# ESP_Updater.net
KiCad netlist of a schematic drawn in EAGLE
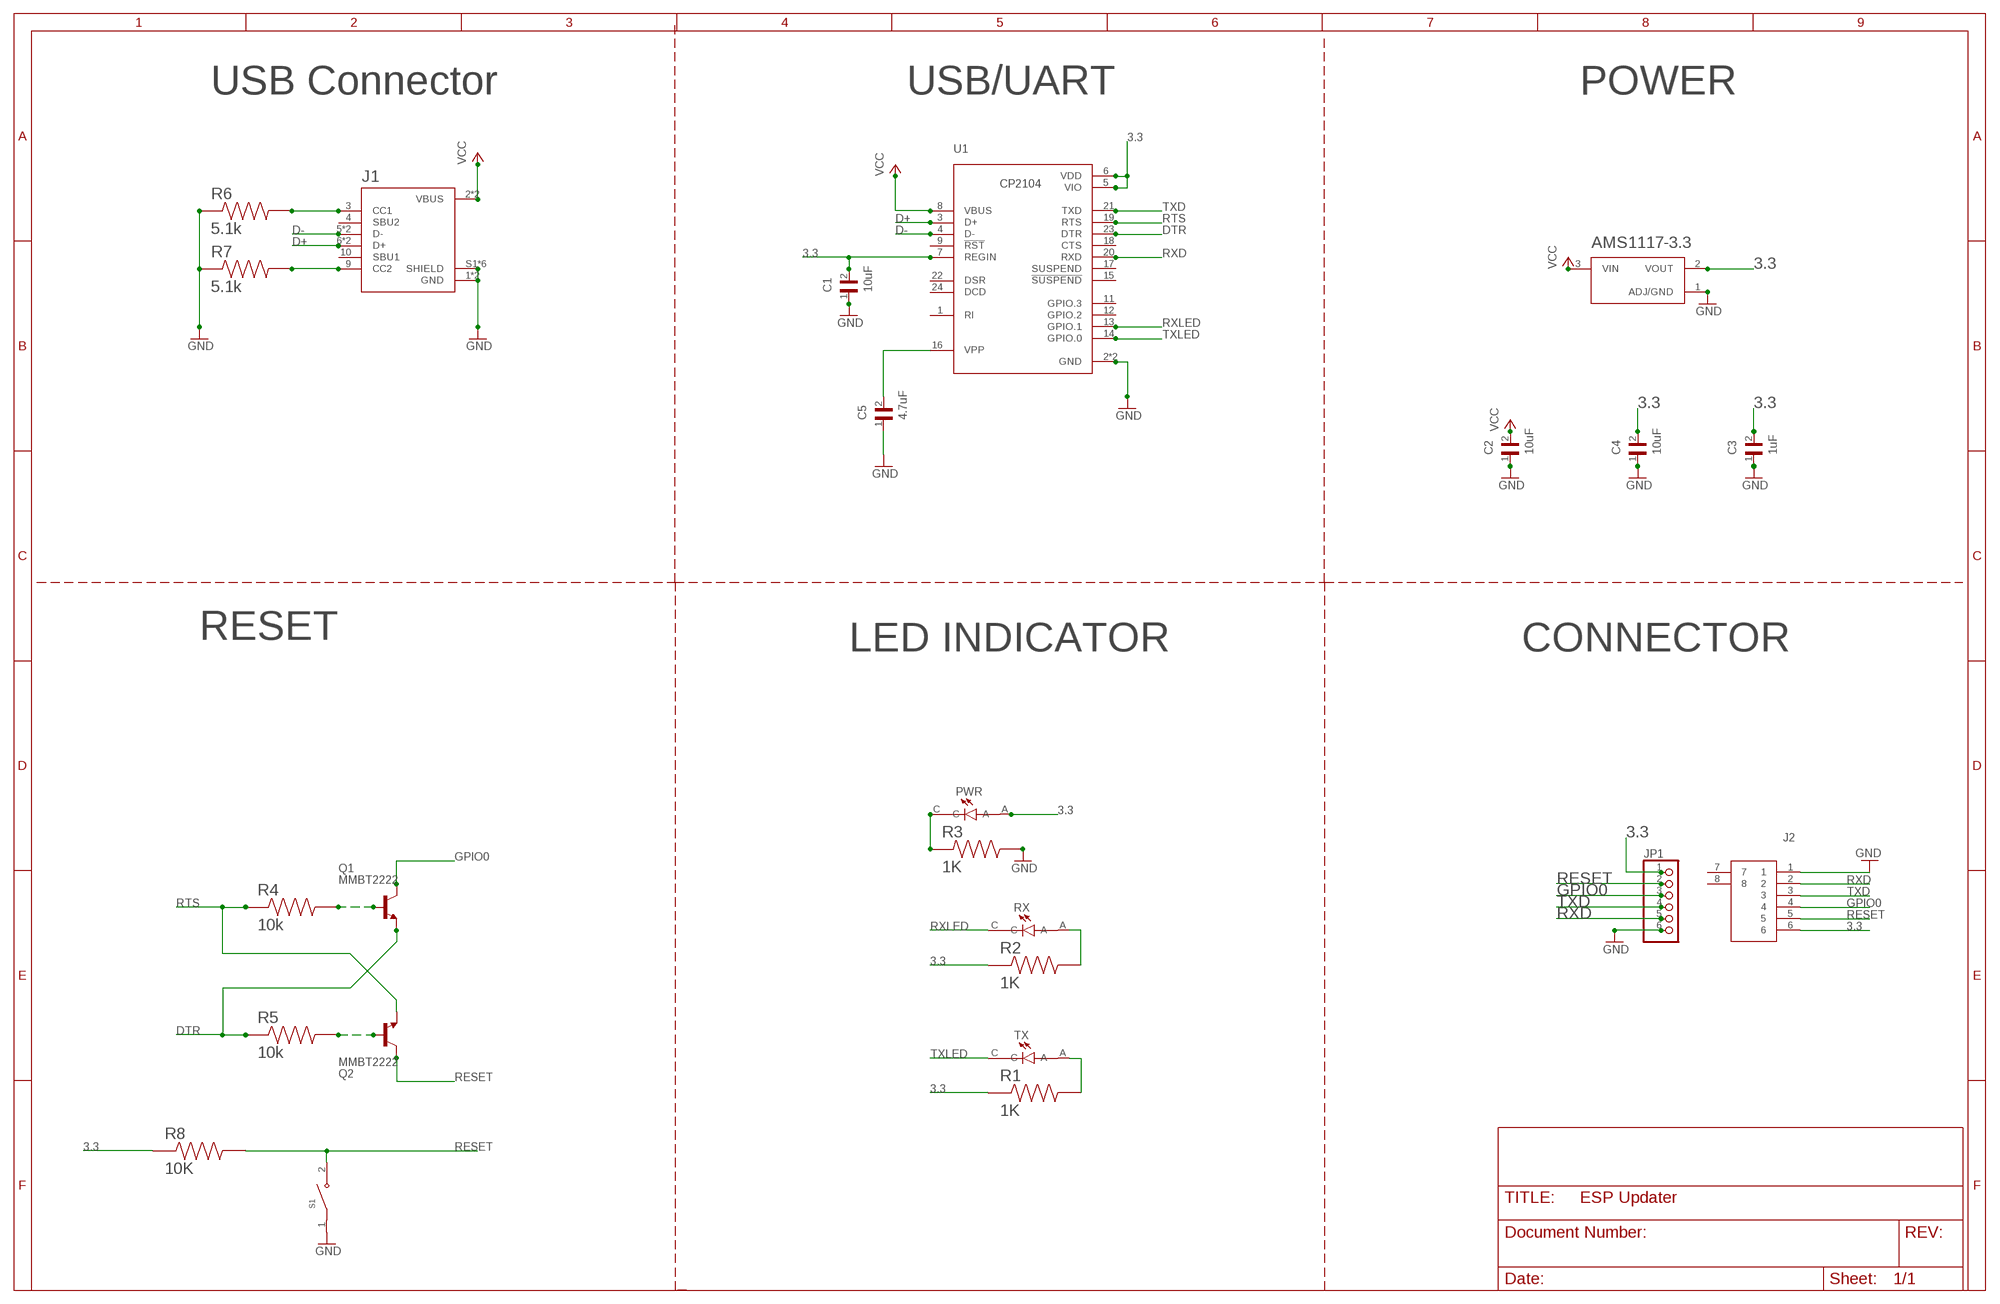
[diagram p0: schematic, sheet 1]

(export (version "E")
  (design (tool "Eeschema 10.0.6"))
  (components
    (comp (ref "C1")
      (value "10uF")
      (footprint "eagle-import:CAPC2012X94N")
      (fields (field (name "MF") "AVX") (field (name "MP") "0805YC103J4T2A"))
      (libsource (lib "eagle-import") (part "0805YC103J4T2A"))
    )
    (comp (ref "C2")
      (value "10uF")
      (footprint "eagle-import:CAPC2012X94N")
      (fields (field (name "MF") "AVX") (field (name "MP") "0805YC103J4T2A"))
      (libsource (lib "eagle-import") (part "0805YC103J4T2A"))
    )
    (comp (ref "C3")
      (value "1uF")
      (footprint "eagle-import:CAPC2012X94N")
      (fields (field (name "MF") "AVX") (field (name "MP") "0805YC103J4T2A"))
      (libsource (lib "eagle-import") (part "0805YC103J4T2A"))
    )
    (comp (ref "C4")
      (value "10uF")
      (footprint "eagle-import:CAPC2012X94N")
      (fields (field (name "MF") "AVX") (field (name "MP") "0805YC103J4T2A"))
      (libsource (lib "eagle-import") (part "0805YC103J4T2A"))
    )
    (comp (ref "C5")
      (value "4.7uF")
      (footprint "eagle-import:CAPC2012X94N")
      (fields (field (name "MF") "AVX") (field (name "MP") "0805YC103J4T2A"))
      (libsource (lib "eagle-import") (part "0805YC103J4T2A"))
    )
    (comp (ref "J1")
      (value "DX07S016JA1R1500")
      (footprint "eagle-import:JAE_DX07S016JA1R1500")
      (fields (field (name "MF") "JAE Electronics"))
      (libsource (lib "eagle-import") (part "DX07S016JA1R1500"))
    )
    (comp (ref "J2")
      (value "52852-0670")
      (footprint "eagle-import:528520670")
      (fields (field (name "MOUSER_PART_NUMBER") "538-52852-0670"))
      (libsource (lib "eagle-import") (part "52852-0670"))
    )
    (comp (ref "JP1")
      (value "PINHD-1X6")
      (footprint "eagle-import:1X06")
      (libsource (lib "eagle-import") (part "PINHD-1X6"))
    )
    (comp (ref "PWR")
      (value "SML-LXT0805IW-TR")
      (footprint "eagle-import:LEDC2012X120N")
      (fields (field (name "MF") "Lumex Opto/Components"))
      (libsource (lib "eagle-import") (part "SML-LXT0805IW-TR"))
    )
    (comp (ref "Q1")
      (value "MMBT2222")
      (footprint "eagle-import:SOT23-BEC")
      (fields (field (name "MF") "ON Semiconductor"))
      (libsource (lib "eagle-import") (part "MMBT2222"))
    )
    (comp (ref "Q2")
      (value "MMBT2222")
      (footprint "eagle-import:SOT23-BEC")
      (fields (field (name "MF") "ON Semiconductor"))
      (libsource (lib "eagle-import") (part "MMBT2222"))
    )
    (comp (ref "R1")
      (value "1K")
      (footprint "eagle-import:RESC2012X60N")
      (fields (field (name "MF") "Yageo") (field (name "MP") "RC0805FR-07330RL"))
      (libsource (lib "eagle-import") (part "RC0805FR-07330RL"))
    )
    (comp (ref "R2")
      (value "1K")
      (footprint "eagle-import:RESC2012X60N")
      (fields (field (name "MF") "Yageo") (field (name "MP") "RC0805FR-07330RL"))
      (libsource (lib "eagle-import") (part "RC0805FR-07330RL"))
    )
    (comp (ref "R3")
      (value "1K")
      (footprint "eagle-import:RESC2012X60N")
      (fields (field (name "MF") "Yageo") (field (name "MP") "RC0805FR-07330RL"))
      (libsource (lib "eagle-import") (part "RC0805FR-07330RL"))
    )
    (comp (ref "R4")
      (value "10k")
      (footprint "eagle-import:RESC2012X60N")
      (fields (field (name "MF") "Yageo") (field (name "MP") "RC0805FR-07330RL"))
      (libsource (lib "eagle-import") (part "RC0805FR-07330RL"))
    )
    (comp (ref "R5")
      (value "10k")
      (footprint "eagle-import:RESC2012X60N")
      (fields (field (name "MF") "Yageo") (field (name "MP") "RC0805FR-07330RL"))
      (libsource (lib "eagle-import") (part "RC0805FR-07330RL"))
    )
    (comp (ref "R6")
      (value "5.1k")
      (footprint "eagle-import:RESC2012X60N")
      (fields (field (name "MF") "Yageo") (field (name "MP") "RC0805FR-07330RL"))
      (libsource (lib "eagle-import") (part "RC0805FR-07330RL"))
    )
    (comp (ref "R7")
      (value "5.1k")
      (footprint "eagle-import:RESC2012X60N")
      (fields (field (name "MF") "Yageo") (field (name "MP") "RC0805FR-07330RL"))
      (libsource (lib "eagle-import") (part "RC0805FR-07330RL"))
    )
    (comp (ref "R8")
      (value "10K")
      (footprint "eagle-import:RESC2012X60N")
      (fields (field (name "MF") "Yageo") (field (name "MP") "RC0805FR-07330RL"))
      (libsource (lib "eagle-import") (part "RC0805FR-07330RL"))
    )
    (comp (ref "RX")
      (value "SML-LXT0805IW-TR")
      (footprint "eagle-import:LEDC2012X120N")
      (fields (field (name "MF") "Lumex Opto/Components"))
      (libsource (lib "eagle-import") (part "SML-LXT0805IW-TR"))
    )
    (comp (ref "S1")
      (value "PTS636_SM43J_SMTR_LFS")
      (footprint "eagle-import:SW_PTS636_SM43J_SMTR_LFS")
      (fields (field (name "MF") "C&K") (field (name "MP") "PTS636 SM43J SMTR LFS"))
      (libsource (lib "eagle-import") (part "PTS636_SM43J_SMTR_LFS"))
    )
    (comp (ref "TX")
      (value "SML-LXT0805IW-TR")
      (footprint "eagle-import:LEDC2012X120N")
      (fields (field (name "MF") "Lumex Opto/Components"))
      (libsource (lib "eagle-import") (part "SML-LXT0805IW-TR"))
    )
    (comp (ref "U1")
      (value "CP2104")
      (footprint "eagle-import:QFN50P400X400X80-25N")
      (fields (field (name "MF") "Silicon Labs") (field (name "MP") "CP2104-F03-GM"))
      (libsource (lib "eagle-import") (part "CP2104-F03-GM"))
    )
    (comp (ref "U2")
      (value "AMS1117-3.3")
      (footprint "eagle-import:SOT229P700X180-4N")
      (fields (field (name "MF") "Advanced Monolithic Systems"))
      (libsource (lib "eagle-import") (part "AMS1117-3.3"))
    )
  )
  (nets
    (net (code "1") (name "/3.3") (class "Default")
      (node (ref "C1") (pin "2") (pinfunction "2_2") (pintype "passive"))
      (node (ref "C3") (pin "2") (pinfunction "2_2") (pintype "passive"))
      (node (ref "C4") (pin "2") (pinfunction "2_2") (pintype "passive"))
      (node (ref "J2") (pin "6") (pinfunction "6_6") (pintype "bidirectional"))
      (node (ref "JP1") (pin "1") (pinfunction "1_1") (pintype "passive"))
      (node (ref "PWR") (pin "A") (pinfunction "A_A") (pintype "passive"))
      (node (ref "R1") (pin "1") (pinfunction "1_1") (pintype "passive"))
      (node (ref "R2") (pin "1") (pinfunction "1_1") (pintype "passive"))
      (node (ref "R8") (pin "1") (pinfunction "1_1") (pintype "passive"))
      (node (ref "U1") (pin "5") (pinfunction "VIO_5") (pintype "power_in"))
      (node (ref "U1") (pin "6") (pinfunction "VDD_6") (pintype "power_in"))
      (node (ref "U1") (pin "7") (pinfunction "REGIN_7") (pintype "input"))
      (node (ref "U2") (pin "2") (pinfunction "VOUT_2") (pintype "output"))
    )
    (net (code "2") (name "/D+") (class "Default")
      (node (ref "J1") (pin "6") (pinfunction "D+_6") (pintype "passive"))
      (node (ref "J1") (pin "7") (pinfunction "D+_7") (pintype "passive"))
      (node (ref "U1") (pin "3") (pinfunction "D+_3") (pintype "bidirectional"))
    )
    (net (code "3") (name "/D-") (class "Default")
      (node (ref "J1") (pin "5") (pinfunction "D-_5") (pintype "passive"))
      (node (ref "J1") (pin "8") (pinfunction "D-_8") (pintype "passive"))
      (node (ref "U1") (pin "4") (pinfunction "D-_4") (pintype "bidirectional"))
    )
    (net (code "4") (name "/DTR") (class "Default")
      (node (ref "Q1") (pin "E") (pinfunction "E_E") (pintype "passive"))
      (node (ref "R5") (pin "1") (pinfunction "1_1") (pintype "passive"))
      (node (ref "U1") (pin "23") (pinfunction "DTR_23") (pintype "output"))
    )
    (net (code "5") (name "/GPIO0") (class "Default")
      (node (ref "J2") (pin "4") (pinfunction "4_4") (pintype "bidirectional"))
      (node (ref "JP1") (pin "3") (pinfunction "3_3") (pintype "passive"))
      (node (ref "Q1") (pin "C") (pinfunction "C_C") (pintype "passive"))
    )
    (net (code "6") (name "/RESET") (class "Default")
      (node (ref "J2") (pin "5") (pinfunction "5_5") (pintype "bidirectional"))
      (node (ref "JP1") (pin "2") (pinfunction "2_2") (pintype "passive"))
      (node (ref "Q2") (pin "C") (pinfunction "C_C") (pintype "passive"))
      (node (ref "R8") (pin "2") (pinfunction "2_2") (pintype "passive"))
      (node (ref "S1") (pin "2") (pinfunction "NO_2") (pintype "passive"))
    )
    (net (code "7") (name "/RTS") (class "Default")
      (node (ref "Q2") (pin "E") (pinfunction "E_E") (pintype "passive"))
      (node (ref "R4") (pin "1") (pinfunction "1_1") (pintype "passive"))
      (node (ref "U1") (pin "19") (pinfunction "RTS_19") (pintype "output"))
    )
    (net (code "8") (name "/RXD") (class "Default")
      (node (ref "J2") (pin "2") (pinfunction "2_2") (pintype "bidirectional"))
      (node (ref "JP1") (pin "5") (pinfunction "5_5") (pintype "passive"))
      (node (ref "U1") (pin "20") (pinfunction "RXD_20") (pintype "input"))
    )
    (net (code "9") (name "/RXLED") (class "Default")
      (node (ref "RX") (pin "C") (pinfunction "C_C") (pintype "passive"))
      (node (ref "U1") (pin "13") (pinfunction "GPIO.1_13") (pintype "bidirectional"))
    )
    (net (code "10") (name "/TXD") (class "Default")
      (node (ref "J2") (pin "3") (pinfunction "3_3") (pintype "bidirectional"))
      (node (ref "JP1") (pin "4") (pinfunction "4_4") (pintype "passive"))
      (node (ref "U1") (pin "21") (pinfunction "TXD_21") (pintype "output"))
    )
    (net (code "11") (name "/TXLED") (class "Default")
      (node (ref "TX") (pin "C") (pinfunction "C_C") (pintype "passive"))
      (node (ref "U1") (pin "14") (pinfunction "GPIO.0_14") (pintype "bidirectional"))
    )
    (net (code "12") (name "GND") (class "Default")
      (node (ref "C1") (pin "1") (pinfunction "1_1") (pintype "passive"))
      (node (ref "C2") (pin "1") (pinfunction "1_1") (pintype "passive"))
      (node (ref "C3") (pin "1") (pinfunction "1_1") (pintype "passive"))
      (node (ref "C4") (pin "1") (pinfunction "1_1") (pintype "passive"))
      (node (ref "C5") (pin "1") (pinfunction "1_1") (pintype "passive"))
      (node (ref "J1") (pin "1") (pinfunction "GND_1") (pintype "power_in"))
      (node (ref "J1") (pin "12") (pinfunction "GND_12") (pintype "power_in"))
      (node (ref "J1") (pin "S1") (pinfunction "SHIELD_S1") (pintype "passive"))
      (node (ref "J1") (pin "S2") (pinfunction "SHIELD_S2") (pintype "passive"))
      (node (ref "J1") (pin "S3") (pinfunction "SHIELD_S3") (pintype "passive"))
      (node (ref "J1") (pin "S4") (pinfunction "SHIELD_S4") (pintype "passive"))
      (node (ref "J1") (pin "S5") (pinfunction "SHIELD_S5") (pintype "passive"))
      (node (ref "J1") (pin "S6") (pinfunction "SHIELD_S6") (pintype "passive"))
      (node (ref "J2") (pin "1") (pinfunction "1_1") (pintype "bidirectional"))
      (node (ref "JP1") (pin "6") (pinfunction "6_6") (pintype "passive"))
      (node (ref "R3") (pin "2") (pinfunction "2_2") (pintype "passive"))
      (node (ref "R6") (pin "1") (pinfunction "1_1") (pintype "passive"))
      (node (ref "R7") (pin "1") (pinfunction "1_1") (pintype "passive"))
      (node (ref "S1") (pin "1") (pinfunction "COM_1") (pintype "passive"))
      (node (ref "U1") (pin "2") (pinfunction "GND_2") (pintype "power_in"))
      (node (ref "U1") (pin "25") (pinfunction "GND_25") (pintype "power_in"))
      (node (ref "U2") (pin "1") (pinfunction "ADJ/GND_1") (pintype "power_in"))
    )
    (net (code "13") (name "Net-(J1-CC1)") (class "Default")
      (node (ref "J1") (pin "3") (pinfunction "CC1_3") (pintype "passive"))
      (node (ref "R6") (pin "2") (pinfunction "2_2") (pintype "passive"))
    )
    (net (code "14") (name "Net-(J1-CC2)") (class "Default")
      (node (ref "J1") (pin "9") (pinfunction "CC2_9") (pintype "passive"))
      (node (ref "R7") (pin "2") (pinfunction "2_2") (pintype "passive"))
    )
    (net (code "15") (name "Net-(PWR-PadC)") (class "Default")
      (node (ref "PWR") (pin "C") (pinfunction "C_C") (pintype "passive"))
      (node (ref "R3") (pin "1") (pinfunction "1_1") (pintype "passive"))
    )
    (net (code "16") (name "Net-(Q1-PadB)") (class "Default")
      (node (ref "Q1") (pin "B") (pinfunction "B_B") (pintype "passive"))
      (node (ref "R4") (pin "2") (pinfunction "2_2") (pintype "passive"))
    )
    (net (code "17") (name "Net-(Q2-PadB)") (class "Default")
      (node (ref "Q2") (pin "B") (pinfunction "B_B") (pintype "passive"))
      (node (ref "R5") (pin "2") (pinfunction "2_2") (pintype "passive"))
    )
    (net (code "18") (name "Net-(R1-Pad2)") (class "Default")
      (node (ref "R1") (pin "2") (pinfunction "2_2") (pintype "passive"))
      (node (ref "TX") (pin "A") (pinfunction "A_A") (pintype "passive"))
    )
    (net (code "19") (name "Net-(R2-Pad2)") (class "Default")
      (node (ref "R2") (pin "2") (pinfunction "2_2") (pintype "passive"))
      (node (ref "RX") (pin "A") (pinfunction "A_A") (pintype "passive"))
    )
    (net (code "20") (name "Net-(U1-VPP)") (class "Default")
      (node (ref "C5") (pin "2") (pinfunction "2_2") (pintype "passive"))
      (node (ref "U1") (pin "16") (pinfunction "VPP_16") (pintype "passive"))
    )
    (net (code "21") (name "VCC") (class "Default")
      (node (ref "C2") (pin "2") (pinfunction "2_2") (pintype "passive"))
      (node (ref "J1") (pin "11") (pinfunction "VBUS_11") (pintype "power_in"))
      (node (ref "J1") (pin "2") (pinfunction "VBUS_2") (pintype "power_in"))
      (node (ref "U1") (pin "8") (pinfunction "VBUS_8") (pintype "input"))
      (node (ref "U2") (pin "3") (pinfunction "VIN_3") (pintype "input"))
    )
    (net (code "22") (name "unconnected-(J1-SBU1-Pad10)") (class "Default")
      (node (ref "J1") (pin "10") (pinfunction "SBU1_10") (pintype "passive"))
    )
    (net (code "23") (name "unconnected-(J1-SBU2-Pad4)") (class "Default")
      (node (ref "J1") (pin "4") (pinfunction "SBU2_4") (pintype "passive"))
    )
    (net (code "24") (name "unconnected-(J2-Pad7)") (class "Default")
      (node (ref "J2") (pin "7") (pinfunction "7_7") (pintype "bidirectional"))
    )
    (net (code "25") (name "unconnected-(J2-Pad8)") (class "Default")
      (node (ref "J2") (pin "8") (pinfunction "8_8") (pintype "bidirectional"))
    )
    (net (code "26") (name "unconnected-(U1-CTS-Pad18)") (class "Default")
      (node (ref "U1") (pin "18") (pinfunction "CTS_18") (pintype "input"))
    )
    (net (code "27") (name "unconnected-(U1-DCD-Pad24)") (class "Default")
      (node (ref "U1") (pin "24") (pinfunction "DCD_24") (pintype "input"))
    )
    (net (code "28") (name "unconnected-(U1-DSR-Pad22)") (class "Default")
      (node (ref "U1") (pin "22") (pinfunction "DSR_22") (pintype "input"))
    )
    (net (code "29") (name "unconnected-(U1-GPIO.2-Pad12)") (class "Default")
      (node (ref "U1") (pin "12") (pinfunction "GPIO.2_12") (pintype "bidirectional"))
    )
    (net (code "30") (name "unconnected-(U1-GPIO.3-Pad11)") (class "Default")
      (node (ref "U1") (pin "11") (pinfunction "GPIO.3_11") (pintype "bidirectional"))
    )
    (net (code "31") (name "unconnected-(U1-RI-Pad1)") (class "Default")
      (node (ref "U1") (pin "1") (pinfunction "RI_1") (pintype "input"))
    )
    (net (code "32") (name "unconnected-(U1-SUSPEND-Pad17)") (class "Default")
      (node (ref "U1") (pin "17") (pinfunction "SUSPEND_17") (pintype "output"))
    )
    (net (code "33") (name "unconnected-(U1-~{RST}-Pad9)") (class "Default")
      (node (ref "U1") (pin "9") (pinfunction "~{RST}_9") (pintype "input"))
    )
    (net (code "34") (name "unconnected-(U1-~{SUSPEND}-Pad15)") (class "Default")
      (node (ref "U1") (pin "15") (pinfunction "~{SUSPEND}_15") (pintype "output"))
    )
  )
)
